# Schematic_v36.net
KiCad netlist of a schematic drawn in EAGLE
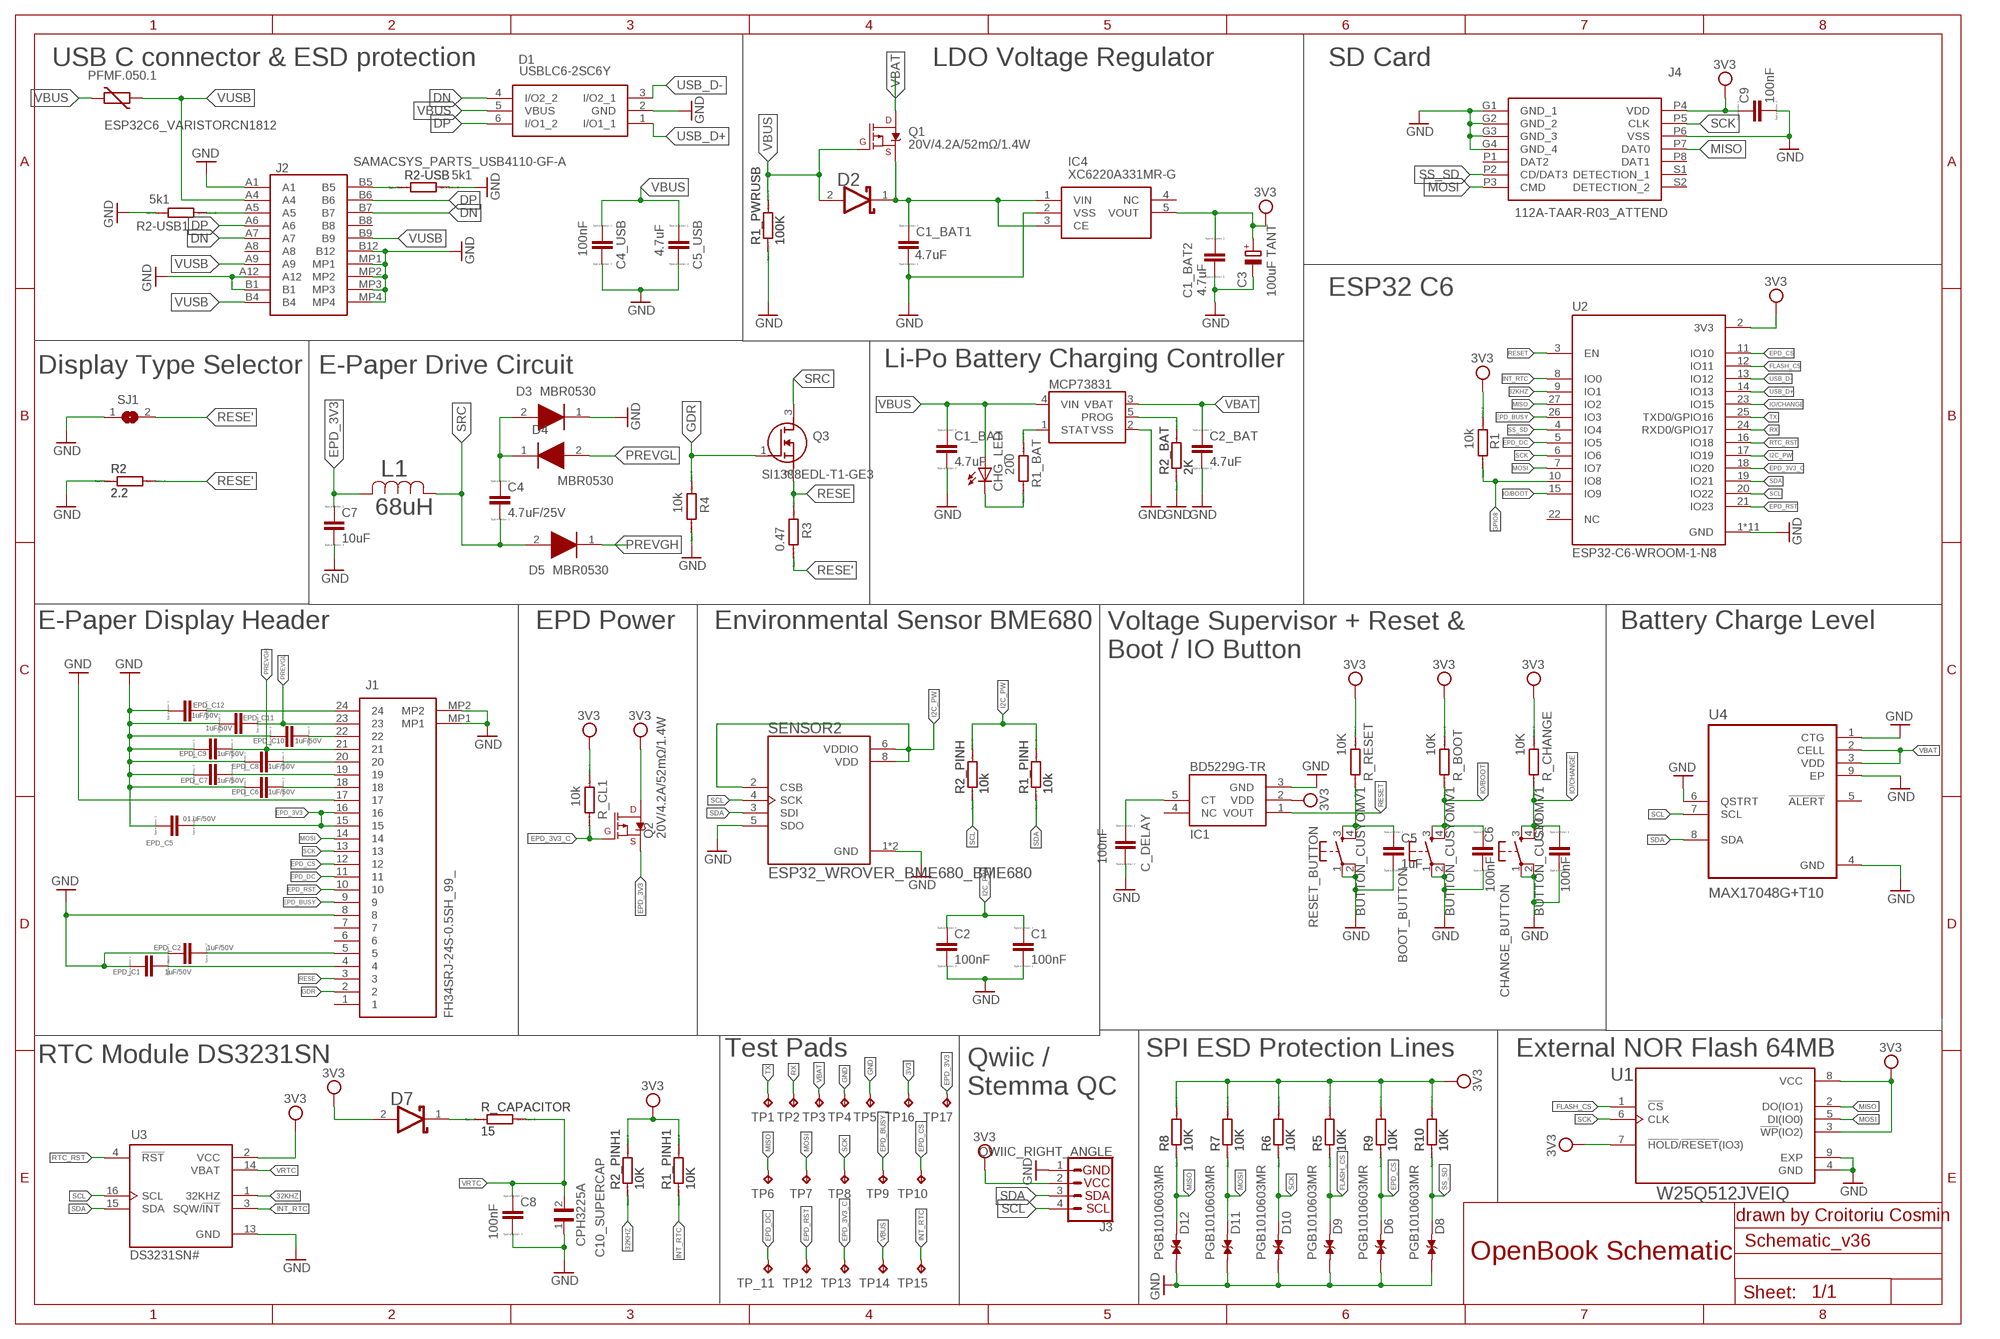
[diagram p0: schematic, sheet 1]

(export (version "E")
  (design (tool "Eeschema 10.0.6"))
  (components
    (comp (ref "BOOT_BUTTON")
      (value "BUTTON_CUSYOMV1")
      (footprint "eagle-import:MYBUTTON")
      (libsource (lib "eagle-import") (part "BUTTON_CUSYOMV1"))
    )
    (comp (ref "C1")
      (value "100nF")
      (footprint "eagle-import:EAGLE-LTSPICE_C0402")
      (libsource (lib "eagle-import") (part "EAGLE-LTSPICE_CC0402"))
    )
    (comp (ref "C1_BAT")
      (value "4.7uF")
      (footprint "eagle-import:EAGLE-LTSPICE_C0402")
      (libsource (lib "eagle-import") (part "EAGLE-LTSPICE_CC0402"))
    )
    (comp (ref "C1_BAT1")
      (value "4.7uF")
      (footprint "eagle-import:EAGLE-LTSPICE_C0402")
      (libsource (lib "eagle-import") (part "ESP32_WROVER_EAGLE-LTSPICE_CC0402"))
    )
    (comp (ref "C1_BAT2")
      (value "4.7uF")
      (footprint "eagle-import:EAGLE-LTSPICE_C0402")
      (libsource (lib "eagle-import") (part "ESP32_WROVER_EAGLE-LTSPICE_CC0402"))
    )
    (comp (ref "C2")
      (value "100nF")
      (footprint "eagle-import:EAGLE-LTSPICE_C0402")
      (libsource (lib "eagle-import") (part "EAGLE-LTSPICE_CC0402"))
    )
    (comp (ref "C2_BAT")
      (value "4.7uF")
      (footprint "eagle-import:EAGLE-LTSPICE_C0402")
      (libsource (lib "eagle-import") (part "EAGLE-LTSPICE_CC0402"))
    )
    (comp (ref "C3")
      (value "100uF TANT")
      (footprint "eagle-import:RCL_CT3528")
      (libsource (lib "eagle-import") (part "RCL_CPOL-EUCT3528"))
    )
    (comp (ref "C4")
      (value "4.7uF/25V")
      (footprint "eagle-import:EAGLE-LTSPICE_C0402")
      (libsource (lib "eagle-import") (part "EAGLE-LTSPICE_CC0402"))
    )
    (comp (ref "C4_USB")
      (value "100nF")
      (footprint "eagle-import:EAGLE-LTSPICE_C0402")
      (libsource (lib "eagle-import") (part "EAGLE-LTSPICE_CC0402"))
    )
    (comp (ref "C5")
      (value "1uF")
      (footprint "eagle-import:EAGLE-LTSPICE_C0402")
      (libsource (lib "eagle-import") (part "EAGLE-LTSPICE_CC0402"))
    )
    (comp (ref "C5_USB")
      (value "4.7uF")
      (footprint "eagle-import:EAGLE-LTSPICE_C0402")
      (libsource (lib "eagle-import") (part "EAGLE-LTSPICE_CC0402"))
    )
    (comp (ref "C6")
      (value "100nF")
      (footprint "eagle-import:EAGLE-LTSPICE_C0402")
      (libsource (lib "eagle-import") (part "EAGLE-LTSPICE_CC0402"))
    )
    (comp (ref "C7")
      (value "10uF")
      (footprint "eagle-import:EAGLE-LTSPICE_C0402")
      (libsource (lib "eagle-import") (part "EAGLE-LTSPICE_CC0402"))
    )
    (comp (ref "C8")
      (value "100nF")
      (footprint "eagle-import:EAGLE-LTSPICE_C0402")
      (libsource (lib "eagle-import") (part "EAGLE-LTSPICE_CC0402"))
    )
    (comp (ref "C9")
      (value "100nF")
      (footprint "eagle-import:EAGLE-LTSPICE_C0402")
      (libsource (lib "eagle-import") (part "EAGLE-LTSPICE_CC0402"))
    )
    (comp (ref "C10")
      (value "100nF")
      (footprint "eagle-import:EAGLE-LTSPICE_C0402")
      (libsource (lib "eagle-import") (part "EAGLE-LTSPICE_CC0402"))
    )
    (comp (ref "C10_SUPERCAP")
      (value "CPH3225A")
      (footprint "eagle-import:CAPCP3225X100N")
      (fields (field (name "MF") "Seiko Instruments"))
      (libsource (lib "eagle-import") (part "CPH3225A"))
    )
    (comp (ref "CHANGE_BUTTON")
      (value "BUTTON_CUSYOMV1")
      (footprint "eagle-import:MYBUTTON")
      (libsource (lib "eagle-import") (part "BUTTON_CUSYOMV1"))
    )
    (comp (ref "CHG_LED")
      (value "ADAFRUIT_LEDCHIP-LED0603")
      (footprint "eagle-import:ADAFRUIT_CHIP-LED0603")
      (libsource (lib "eagle-import") (part "ADAFRUIT_LEDCHIP-LED0603"))
    )
    (comp (ref "C_DELAY")
      (value "100nF")
      (footprint "eagle-import:EAGLE-LTSPICE_C0402")
      (libsource (lib "eagle-import") (part "EAGLE-LTSPICE_CC0402"))
    )
    (comp (ref "D1")
      (value "USBLC6-2SC6Y")
      (footprint "eagle-import:SOT95P280X145-6N")
      (fields (field (name "MF") "STMicroelectronics"))
      (libsource (lib "eagle-import") (part "USBLC6-2SC6Y"))
    )
    (comp (ref "D2")
      (value "ESP32_WROVER_AVX---SD0805S020S1R0_AVX_SD0805S020S1R0_0_0AVX_SD0805S020S1R0_0_0")
      (footprint "eagle-import:ESP32_WROVER_AVX---SD0805S020S1R0_AVX_SD0805S020S1R0_0")
      (fields
        (field (name "DIGIKEY_PART_NUMBER") "478-7800-1-ND")
        (field (name "MF") "AVX")
        (field (name "MOUSER_PART_NUMBER") "581-SD0805S020S1R0")
      )
      (libsource (lib "eagle-import") (part "ESP32_WROVER_AVX---SD0805S020S1R0_AVX_SD0805S020S1R0_0_0AVX_SD0805S020S1R0_0_0"))
    )
    (comp (ref "D3")
      (value "MBR0530")
      (footprint "eagle-import:SOD3716X135N")
      (fields (field (name "MF") "ON Semiconductor"))
      (libsource (lib "eagle-import") (part "MBR0530"))
    )
    (comp (ref "D4")
      (value "MBR0530")
      (footprint "eagle-import:SOD3716X135N")
      (fields (field (name "MF") "ON Semiconductor"))
      (libsource (lib "eagle-import") (part "MBR0530"))
    )
    (comp (ref "D5")
      (value "MBR0530")
      (footprint "eagle-import:SOD3716X135N")
      (fields (field (name "MF") "ON Semiconductor"))
      (libsource (lib "eagle-import") (part "MBR0530"))
    )
    (comp (ref "D6")
      (value "PGB1010603MR")
      (footprint "eagle-import:DIOC1608X36N")
      (fields (field (name "MF") "Littelfuse Inc."))
      (libsource (lib "eagle-import") (part "PGB1010603MR"))
    )
    (comp (ref "D7")
      (value "ESP32_WROVER_AVX---SD0805S020S1R0_AVX_SD0805S020S1R0_0_0AVX_SD0805S020S1R0_0_0")
      (footprint "eagle-import:ESP32_WROVER_AVX---SD0805S020S1R0_AVX_SD0805S020S1R0_0")
      (fields
        (field (name "DIGIKEY_PART_NUMBER") "478-7800-1-ND")
        (field (name "MF") "AVX")
        (field (name "MOUSER_PART_NUMBER") "581-SD0805S020S1R0")
      )
      (libsource (lib "eagle-import") (part "ESP32_WROVER_AVX---SD0805S020S1R0_AVX_SD0805S020S1R0_0_0AVX_SD0805S020S1R0_0_0"))
    )
    (comp (ref "D8")
      (value "PGB1010603MR")
      (footprint "eagle-import:DIOC1608X36N")
      (fields (field (name "MF") "Littelfuse Inc."))
      (libsource (lib "eagle-import") (part "PGB1010603MR"))
    )
    (comp (ref "D9")
      (value "PGB1010603MR")
      (footprint "eagle-import:DIOC1608X36N")
      (fields (field (name "MF") "Littelfuse Inc."))
      (libsource (lib "eagle-import") (part "PGB1010603MR"))
    )
    (comp (ref "D10")
      (value "PGB1010603MR")
      (footprint "eagle-import:DIOC1608X36N")
      (fields (field (name "MF") "Littelfuse Inc."))
      (libsource (lib "eagle-import") (part "PGB1010603MR"))
    )
    (comp (ref "D11")
      (value "PGB1010603MR")
      (footprint "eagle-import:DIOC1608X36N")
      (fields (field (name "MF") "Littelfuse Inc."))
      (libsource (lib "eagle-import") (part "PGB1010603MR"))
    )
    (comp (ref "D12")
      (value "PGB1010603MR")
      (footprint "eagle-import:DIOC1608X36N")
      (fields (field (name "MF") "Littelfuse Inc."))
      (libsource (lib "eagle-import") (part "PGB1010603MR"))
    )
    (comp (ref "EPD_C1")
      (value "1uF/50V")
      (footprint "eagle-import:EAGLE-LTSPICE_C0402")
      (libsource (lib "eagle-import") (part "EAGLE-LTSPICE_CC0402"))
    )
    (comp (ref "EPD_C2")
      (value "1uF/50V")
      (footprint "eagle-import:EAGLE-LTSPICE_C0402")
      (libsource (lib "eagle-import") (part "EAGLE-LTSPICE_CC0402"))
    )
    (comp (ref "EPD_C5")
      (value "01.uF/50V")
      (footprint "eagle-import:EAGLE-LTSPICE_C0402")
      (libsource (lib "eagle-import") (part "EAGLE-LTSPICE_CC0402"))
    )
    (comp (ref "EPD_C6")
      (value "1uF/50V")
      (footprint "eagle-import:EAGLE-LTSPICE_C0402")
      (libsource (lib "eagle-import") (part "EAGLE-LTSPICE_CC0402"))
    )
    (comp (ref "EPD_C7")
      (value "1uF/50V")
      (footprint "eagle-import:EAGLE-LTSPICE_C0402")
      (libsource (lib "eagle-import") (part "EAGLE-LTSPICE_CC0402"))
    )
    (comp (ref "EPD_C8")
      (value "1uF/50V")
      (footprint "eagle-import:EAGLE-LTSPICE_C0402")
      (libsource (lib "eagle-import") (part "EAGLE-LTSPICE_CC0402"))
    )
    (comp (ref "EPD_C9")
      (value "1uF/50V")
      (footprint "eagle-import:EAGLE-LTSPICE_C0402")
      (libsource (lib "eagle-import") (part "EAGLE-LTSPICE_CC0402"))
    )
    (comp (ref "EPD_C10")
      (value "1uF/50V")
      (footprint "eagle-import:EAGLE-LTSPICE_C0402")
      (libsource (lib "eagle-import") (part "EAGLE-LTSPICE_CC0402"))
    )
    (comp (ref "EPD_C11")
      (value "1uF/50V")
      (footprint "eagle-import:EAGLE-LTSPICE_C0402")
      (libsource (lib "eagle-import") (part "EAGLE-LTSPICE_CC0402"))
    )
    (comp (ref "EPD_C12")
      (value "1uF/50V")
      (footprint "eagle-import:EAGLE-LTSPICE_C0402")
      (libsource (lib "eagle-import") (part "EAGLE-LTSPICE_CC0402"))
    )
    (comp (ref "IC1")
      (value "BD5229G-TR")
      (footprint "eagle-import:SOT95P280X125-5N")
      (fields (field (name "MOUSER_PART_NUMBER") "755-BD5229G-TR"))
      (libsource (lib "eagle-import") (part "BD5229G-TR"))
    )
    (comp (ref "IC4")
      (value "XC6220A331MR-G")
      (footprint "eagle-import:SOT95P280X120-5N")
      (fields (field (name "MOUSER_PART_NUMBER") "865-XC6220A331MR-G"))
      (libsource (lib "eagle-import") (part "XC6220A331MR-G"))
    )
    (comp (ref "J1")
      (value "FH34SRJ-24S-0.5SH_99_")
      (footprint "eagle-import:FH34SRJ24S05SH99")
      (fields
        (field (name "MANUFACTURER_PART_NUMBER") "FH34SRJ-24S-0.5SH(99)")
        (field (name "MOUSER_PART_NUMBER") "798-FH34SRJ24S05SH99")
      )
      (libsource (lib "eagle-import") (part "FH34SRJ-24S-0.5SH_99_"))
    )
    (comp (ref "J2")
      (value "SAMACSYS_PARTS_USB4110-GF-A")
      (footprint "eagle-import:SAMACSYS_PARTS_USB4110GFA")
      (fields
        (field (name "MANUFACTURER_PART_NUMBER") "USB4110-GF-A")
        (field (name "MOUSER_PART_NUMBER") "640-USB4110-GF-A")
      )
      (libsource (lib "eagle-import") (part "SAMACSYS_PARTS_USB4110-GF-A"))
    )
    (comp (ref "J3")
      (value "QWIIC_RIGHT_ANGLE")
      (footprint "eagle-import:JST04_1MM_RA")
      (libsource (lib "eagle-import") (part "QWIIC_CONNECTORJS-1MM"))
    )
    (comp (ref "J4")
      (value "112A-TAAR-R03_ATTEND")
      (footprint "eagle-import:112ATAARR03ATTEND")
      (fields (field (name "MANUFACTURER_PART_NUMBER") "112A-TAAR-R03 ATTEND"))
      (libsource (lib "eagle-import") (part "112A-TAAR-R03_ATTEND"))
    )
    (comp (ref "L1")
      (value "68uH")
      (footprint "eagle-import:IND_4828-WE-TPC_WRE")
      (fields
        (field (name "MANUFACTURER_PART_NUMBER") "744043680")
        (field (name "COPYRIGHT") "Copyright (C) 2024 Ultra Librarian. All rights reserved.")
      )
      (libsource (lib "eagle-import") (part "744043680IND_4828-WE-TPC_WRE"))
    )
    (comp (ref "MCP73831")
      (value "ESP32_WROVER_SPARKFUN-IC-POWER_MCP73831")
      (footprint "eagle-import:ESP32_WROVER_SPARKFUN-IC-POWER_SOT23-5")
      (libsource (lib "eagle-import") (part "ESP32_WROVER_SPARKFUN-IC-POWER_MCP73831"))
    )
    (comp (ref "PFMF.050.1")
      (value "ESP32C6_VARISTORCN1812")
      (footprint "eagle-import:ESP32C6_VARISTOR_CT_CN1812")
      (libsource (lib "eagle-import") (part "ESP32C6_VARISTORCN1812"))
    )
    (comp (ref "Q1")
      (value "20V/4.2A/52mΩ/1.4W")
      (footprint "eagle-import:ESP32_WROVER_SPARKFUN-DISCRETESEMI_SOT23-3")
      (libsource (lib "eagle-import") (part "ESP32_WROVER_SPARKFUN-DISCRETESEMI_MOSFET_PCH-DMG2305UX-7"))
    )
    (comp (ref "Q2")
      (value "20V/4.2A/52mΩ/1.4W")
      (footprint "eagle-import:ESP32_WROVER_SPARKFUN-DISCRETESEMI_SOT23-3")
      (libsource (lib "eagle-import") (part "ESP32_WROVER_SPARKFUN-DISCRETESEMI_MOSFET_PCH-DMG2305UX-7"))
    )
    (comp (ref "Q3")
      (value "SI1308EDL-T1-GE3")
      (footprint "eagle-import:SOT65P210X110-3N")
      (fields (field (name "MF") "Vishay Siliconix"))
      (libsource (lib "eagle-import") (part "SI1308EDL-T1-GE3"))
    )
    (comp (ref "R1")
      (value "10k")
      (footprint "eagle-import:ESP32_WROVER_EAGLE-LTSPICE_R0402")
      (libsource (lib "eagle-import") (part "ESP32_WROVER_EAGLE-LTSPICE_RR0402"))
    )
    (comp (ref "R1_BAT")
      (value "200")
      (footprint "eagle-import:ESP32_WROVER_EAGLE-LTSPICE_R0402")
      (libsource (lib "eagle-import") (part "ESP32_WROVER_EAGLE-LTSPICE_RR0402"))
    )
    (comp (ref "R1_PINH")
      (value "10k")
      (footprint "eagle-import:ESP32_WROVER_EAGLE-LTSPICE_R0402")
      (libsource (lib "eagle-import") (part "ESP32_WROVER_EAGLE-LTSPICE_RR0402"))
    )
    (comp (ref "R1_PINH1")
      (value "10K")
      (footprint "eagle-import:ESP32_WROVER_EAGLE-LTSPICE_R0402")
      (libsource (lib "eagle-import") (part "ESP32_WROVER_EAGLE-LTSPICE_RR0402"))
    )
    (comp (ref "R1_PWRUSB")
      (value "100K")
      (footprint "eagle-import:ESP32_WROVER_EAGLE-LTSPICE_R0402")
      (libsource (lib "eagle-import") (part "ESP32_WROVER_EAGLE-LTSPICE_RR0402"))
    )
    (comp (ref "R2")
      (value "2.2")
      (footprint "eagle-import:ESP32_WROVER_EAGLE-LTSPICE_R0402")
      (libsource (lib "eagle-import") (part "ESP32_WROVER_EAGLE-LTSPICE_RR0402"))
    )
    (comp (ref "R2-USB")
      (value "5k1")
      (footprint "eagle-import:ESP32_WROVER_EAGLE-LTSPICE_R0402")
      (libsource (lib "eagle-import") (part "ESP32_WROVER_EAGLE-LTSPICE_RR0402"))
    )
    (comp (ref "R2-USB1")
      (value "5k1")
      (footprint "eagle-import:ESP32_WROVER_EAGLE-LTSPICE_R0402")
      (libsource (lib "eagle-import") (part "ESP32_WROVER_EAGLE-LTSPICE_RR0402"))
    )
    (comp (ref "R2_BAT")
      (value "2K")
      (footprint "eagle-import:ESP32_WROVER_EAGLE-LTSPICE_R0402")
      (libsource (lib "eagle-import") (part "ESP32_WROVER_EAGLE-LTSPICE_RR0402"))
    )
    (comp (ref "R2_PINH")
      (value "10k")
      (footprint "eagle-import:ESP32_WROVER_EAGLE-LTSPICE_R0402")
      (libsource (lib "eagle-import") (part "ESP32_WROVER_EAGLE-LTSPICE_RR0402"))
    )
    (comp (ref "R2_PINH1")
      (value "10K")
      (footprint "eagle-import:ESP32_WROVER_EAGLE-LTSPICE_R0402")
      (libsource (lib "eagle-import") (part "ESP32_WROVER_EAGLE-LTSPICE_RR0402"))
    )
    (comp (ref "R3")
      (value "0.47")
      (footprint "eagle-import:ESP32_WROVER_EAGLE-LTSPICE_R0402")
      (libsource (lib "eagle-import") (part "ESP32_WROVER_EAGLE-LTSPICE_RR0402"))
    )
    (comp (ref "R4")
      (value "10k")
      (footprint "eagle-import:ESP32_WROVER_EAGLE-LTSPICE_R0402")
      (libsource (lib "eagle-import") (part "ESP32_WROVER_EAGLE-LTSPICE_RR0402"))
    )
    (comp (ref "R5")
      (value "10K")
      (footprint "eagle-import:ESP32_WROVER_EAGLE-LTSPICE_R0402")
      (libsource (lib "eagle-import") (part "ESP32_WROVER_EAGLE-LTSPICE_RR0402"))
    )
    (comp (ref "R6")
      (value "10K")
      (footprint "eagle-import:ESP32_WROVER_EAGLE-LTSPICE_R0402")
      (libsource (lib "eagle-import") (part "ESP32_WROVER_EAGLE-LTSPICE_RR0402"))
    )
    (comp (ref "R7")
      (value "10K")
      (footprint "eagle-import:ESP32_WROVER_EAGLE-LTSPICE_R0402")
      (libsource (lib "eagle-import") (part "ESP32_WROVER_EAGLE-LTSPICE_RR0402"))
    )
    (comp (ref "R8")
      (value "10K")
      (footprint "eagle-import:ESP32_WROVER_EAGLE-LTSPICE_R0402")
      (libsource (lib "eagle-import") (part "ESP32_WROVER_EAGLE-LTSPICE_RR0402"))
    )
    (comp (ref "R9")
      (value "10K")
      (footprint "eagle-import:ESP32_WROVER_EAGLE-LTSPICE_R0402")
      (libsource (lib "eagle-import") (part "ESP32_WROVER_EAGLE-LTSPICE_RR0402"))
    )
    (comp (ref "R10")
      (value "10K")
      (footprint "eagle-import:ESP32_WROVER_EAGLE-LTSPICE_R0402")
      (libsource (lib "eagle-import") (part "ESP32_WROVER_EAGLE-LTSPICE_RR0402"))
    )
    (comp (ref "RESET_BUTTON")
      (value "BUTTON_CUSYOMV1")
      (footprint "eagle-import:MYBUTTON")
      (libsource (lib "eagle-import") (part "BUTTON_CUSYOMV1"))
    )
    (comp (ref "R_BOOT")
      (value "10K")
      (footprint "eagle-import:ESP32_WROVER_EAGLE-LTSPICE_R0402")
      (libsource (lib "eagle-import") (part "ESP32_WROVER_EAGLE-LTSPICE_RR0402"))
    )
    (comp (ref "R_CAPACITOR")
      (value "15")
      (footprint "eagle-import:ESP32_WROVER_EAGLE-LTSPICE_R0402")
      (libsource (lib "eagle-import") (part "ESP32_WROVER_EAGLE-LTSPICE_RR0402"))
    )
    (comp (ref "R_CHANGE")
      (value "10K")
      (footprint "eagle-import:ESP32_WROVER_EAGLE-LTSPICE_R0402")
      (libsource (lib "eagle-import") (part "ESP32_WROVER_EAGLE-LTSPICE_RR0402"))
    )
    (comp (ref "R_CL1")
      (value "10k")
      (footprint "eagle-import:ESP32_WROVER_EAGLE-LTSPICE_R0402")
      (libsource (lib "eagle-import") (part "ESP32_WROVER_EAGLE-LTSPICE_RR0402"))
    )
    (comp (ref "R_RESET")
      (value "10K")
      (footprint "eagle-import:ESP32_WROVER_EAGLE-LTSPICE_R0402")
      (libsource (lib "eagle-import") (part "ESP32_WROVER_EAGLE-LTSPICE_RR0402"))
    )
    (comp (ref "SENSOR2")
      (value "ESP32_WROVER_BME680_BME680")
      (footprint "eagle-import:ESP32_WROVER_BME680_PSON80P300X300X100-8N")
      (fields (field (name "MF") "Bosch Sensortec") (field (name "MP") "BME680"))
      (libsource (lib "eagle-import") (part "ESP32_WROVER_BME680_BME680"))
    )
    (comp (ref "SJ1") (value "SJ") (footprint "eagle-import:SJ") (libsource (lib "eagle-import") (part "SJ")))
    (comp (ref "TP1")
      (value "TPTP20R")
      (footprint "eagle-import:TP20R")
      (libsource (lib "eagle-import") (part "TPTP20R"))
    )
    (comp (ref "TP2")
      (value "TPTP20R")
      (footprint "eagle-import:TP20R")
      (libsource (lib "eagle-import") (part "TPTP20R"))
    )
    (comp (ref "TP3")
      (value "TPTP20R")
      (footprint "eagle-import:TP20R")
      (libsource (lib "eagle-import") (part "TPTP20R"))
    )
    (comp (ref "TP4")
      (value "TPTP20R")
      (footprint "eagle-import:TP20R")
      (libsource (lib "eagle-import") (part "TPTP20R"))
    )
    (comp (ref "TP5")
      (value "TPTP20R")
      (footprint "eagle-import:TP20R")
      (libsource (lib "eagle-import") (part "TPTP20R"))
    )
    (comp (ref "TP6")
      (value "TPTP20R")
      (footprint "eagle-import:TP20R")
      (libsource (lib "eagle-import") (part "TPTP20R"))
    )
    (comp (ref "TP7")
      (value "TPTP20R")
      (footprint "eagle-import:TP20R")
      (libsource (lib "eagle-import") (part "TPTP20R"))
    )
    (comp (ref "TP8")
      (value "TPTP20R")
      (footprint "eagle-import:TP20R")
      (libsource (lib "eagle-import") (part "TPTP20R"))
    )
    (comp (ref "TP9")
      (value "TPTP20R")
      (footprint "eagle-import:TP20R")
      (libsource (lib "eagle-import") (part "TPTP20R"))
    )
    (comp (ref "TP10")
      (value "TPTP20R")
      (footprint "eagle-import:TP20R")
      (libsource (lib "eagle-import") (part "TPTP20R"))
    )
    (comp (ref "TP12")
      (value "TPTP20R")
      (footprint "eagle-import:TP20R")
      (libsource (lib "eagle-import") (part "TPTP20R"))
    )
    (comp (ref "TP13")
      (value "TPTP20R")
      (footprint "eagle-import:TP20R")
      (libsource (lib "eagle-import") (part "TPTP20R"))
    )
    (comp (ref "TP14")
      (value "TPTP20R")
      (footprint "eagle-import:TP20R")
      (libsource (lib "eagle-import") (part "TPTP20R"))
    )
    (comp (ref "TP15")
      (value "TPTP20R")
      (footprint "eagle-import:TP20R")
      (libsource (lib "eagle-import") (part "TPTP20R"))
    )
    (comp (ref "TP16")
      (value "TPTP20R")
      (footprint "eagle-import:TP20R")
      (libsource (lib "eagle-import") (part "TPTP20R"))
    )
    (comp (ref "TP17")
      (value "TPTP20R")
      (footprint "eagle-import:TP20R")
      (libsource (lib "eagle-import") (part "TPTP20R"))
    )
    (comp (ref "TP_11")
      (value "TPTP20R")
      (footprint "eagle-import:TP20R")
      (libsource (lib "eagle-import") (part "TPTP20R"))
    )
    (comp (ref "U1")
      (value "W25Q512JVEIQ")
      (footprint "eagle-import:SON127P600X800X80-9N")
      (fields (field (name "MF") "Winbond Electronics"))
      (libsource (lib "eagle-import") (part "W25Q512JVEIQ"))
    )
    (comp (ref "U2")
      (value "ESP32-C6-WROOM-1-N8")
      (footprint "eagle-import:XCVR_ESP32-C6-WROOM-1-N8")
      (fields (field (name "MF") "Espressif Systems"))
      (libsource (lib "eagle-import") (part "ESP32-C6-WROOM-1-N8"))
    )
    (comp (ref "U3")
      (value "DS3231SN#")
      (footprint "eagle-import:SOIC127P1032X265-16N")
      (fields (field (name "MF") "Analog Devices"))
      (libsource (lib "eagle-import") (part "DS3231SN#"))
    )
    (comp (ref "U4")
      (value "MAX17048G+T10")
      (footprint "eagle-import:SON50P200X200X80-9N")
      (fields (field (name "MF") "Analog Devices"))
      (libsource (lib "eagle-import") (part "MAX17048G+T10"))
    )
  )
  (nets
    (net (code "1") (name "3V3") (class "Default")
      (node (ref "C1_BAT2") (pin "2") (pinfunction "2_2") (pintype "passive"))
      (node (ref "C3") (pin "+") (pinfunction "+_+") (pintype "passive"))
      (node (ref "C9") (pin "1") (pinfunction "1_1") (pintype "passive"))
      (node (ref "D7") (pin "2") (pinfunction "ANODE_2") (pintype "bidirectional"))
      (node (ref "IC1") (pin "2") (pinfunction "VDD_2") (pintype "bidirectional"))
      (node (ref "IC4") (pin "5") (pinfunction "VOUT_5") (pintype "bidirectional"))
      (node (ref "J3") (pin "2") (pinfunction "2_2") (pintype "power_in"))
      (node (ref "J4") (pin "P4") (pinfunction "VDD_P4") (pintype "bidirectional"))
      (node (ref "Q2") (pin "3") (pinfunction "D_3") (pintype "bidirectional"))
      (node (ref "R1") (pin "2") (pinfunction "2_2") (pintype "passive"))
      (node (ref "R10") (pin "2") (pinfunction "2_2") (pintype "passive"))
      (node (ref "R1_PINH1") (pin "2") (pinfunction "2_2") (pintype "passive"))
      (node (ref "R2_PINH1") (pin "2") (pinfunction "2_2") (pintype "passive"))
      (node (ref "R5") (pin "2") (pinfunction "2_2") (pintype "passive"))
      (node (ref "R6") (pin "2") (pinfunction "2_2") (pintype "passive"))
      (node (ref "R7") (pin "2") (pinfunction "2_2") (pintype "passive"))
      (node (ref "R8") (pin "2") (pinfunction "2_2") (pintype "passive"))
      (node (ref "R9") (pin "2") (pinfunction "2_2") (pintype "passive"))
      (node (ref "R_BOOT") (pin "2") (pinfunction "2_2") (pintype "passive"))
      (node (ref "R_CHANGE") (pin "2") (pinfunction "2_2") (pintype "passive"))
      (node (ref "R_CL1") (pin "2") (pinfunction "2_2") (pintype "passive"))
      (node (ref "R_RESET") (pin "2") (pinfunction "2_2") (pintype "passive"))
      (node (ref "TP16") (pin "TP") (pinfunction "TP_TP") (pintype "input"))
      (node (ref "U1") (pin "3") (pinfunction "~{WP}(IO2)_3") (pintype "bidirectional"))
      (node (ref "U1") (pin "7") (pinfunction "~{HOLD}/~{RESET}(IO3)_7") (pintype "bidirectional"))
      (node (ref "U1") (pin "8") (pinfunction "VCC_8") (pintype "power_in"))
      (node (ref "U2") (pin "2") (pinfunction "3V3_2") (pintype "power_in"))
      (node (ref "U3") (pin "2") (pinfunction "VCC_2") (pintype "power_in"))
    )
    (net (code "2") (name "32KHZ") (class "Default")
      (node (ref "R2_PINH1") (pin "1") (pinfunction "1_1") (pintype "passive"))
      (node (ref "U2") (pin "9") (pinfunction "IO1_9") (pintype "bidirectional"))
      (node (ref "U3") (pin "1") (pinfunction "32KHZ_1") (pintype "output"))
    )
    (net (code "3") (name "DN") (class "Default")
      (node (ref "D1") (pin "4") (pinfunction "I/O2_2_4") (pintype "bidirectional"))
      (node (ref "J2") (pin "A7") (pinfunction "A7_A7") (pintype "bidirectional"))
      (node (ref "J2") (pin "B7") (pinfunction "B7_B7") (pintype "bidirectional"))
    )
    (net (code "4") (name "DP") (class "Default")
      (node (ref "D1") (pin "6") (pinfunction "I/O1_2_6") (pintype "bidirectional"))
      (node (ref "J2") (pin "A6") (pinfunction "A6_A6") (pintype "bidirectional"))
      (node (ref "J2") (pin "B6") (pinfunction "B6_B6") (pintype "bidirectional"))
    )
    (net (code "5") (name "EPD_3V3") (class "Default")
      (node (ref "C7") (pin "1") (pinfunction "1_1") (pintype "passive"))
      (node (ref "EPD_C5") (pin "2") (pinfunction "2_2") (pintype "passive"))
      (node (ref "J1") (pin "15") (pinfunction "15_15") (pintype "bidirectional"))
      (node (ref "J1") (pin "16") (pinfunction "16_16") (pintype "bidirectional"))
      (node (ref "L1") (pin "2") (pinfunction "2_2") (pintype "passive"))
      (node (ref "Q2") (pin "2") (pinfunction "S_2") (pintype "bidirectional"))
      (node (ref "TP17") (pin "TP") (pinfunction "TP_TP") (pintype "input"))
    )
    (net (code "6") (name "EPD_3V3_C") (class "Default")
      (node (ref "Q2") (pin "1") (pinfunction "G_1") (pintype "bidirectional"))
      (node (ref "R_CL1") (pin "1") (pinfunction "1_1") (pintype "passive"))
      (node (ref "TP13") (pin "TP") (pinfunction "TP_TP") (pintype "input"))
      (node (ref "U2") (pin "18") (pinfunction "IO20_18") (pintype "bidirectional"))
    )
    (net (code "7") (name "EPD_BUSY") (class "Default")
      (node (ref "J1") (pin "9") (pinfunction "9_9") (pintype "bidirectional"))
      (node (ref "TP9") (pin "TP") (pinfunction "TP_TP") (pintype "input"))
      (node (ref "U2") (pin "26") (pinfunction "IO3_26") (pintype "bidirectional"))
    )
    (net (code "8") (name "EPD_CS") (class "Default")
      (node (ref "D6") (pin "2") (pinfunction "2_2") (pintype "passive"))
      (node (ref "J1") (pin "12") (pinfunction "12_12") (pintype "bidirectional"))
      (node (ref "R9") (pin "1") (pinfunction "1_1") (pintype "passive"))
      (node (ref "TP10") (pin "TP") (pinfunction "TP_TP") (pintype "input"))
      (node (ref "U2") (pin "11") (pinfunction "IO10_11") (pintype "bidirectional"))
    )
    (net (code "9") (name "EPD_DC") (class "Default")
      (node (ref "J1") (pin "11") (pinfunction "11_11") (pintype "bidirectional"))
      (node (ref "TP_11") (pin "TP") (pinfunction "TP_TP") (pintype "input"))
      (node (ref "U2") (pin "5") (pinfunction "IO5_5") (pintype "bidirectional"))
    )
    (net (code "10") (name "EPD_RST") (class "Default")
      (node (ref "J1") (pin "10") (pinfunction "10_10") (pintype "bidirectional"))
      (node (ref "TP12") (pin "TP") (pinfunction "TP_TP") (pintype "input"))
      (node (ref "U2") (pin "21") (pinfunction "IO23_21") (pintype "bidirectional"))
    )
    (net (code "11") (name "FLASH_CS") (class "Default")
      (node (ref "D9") (pin "2") (pinfunction "2_2") (pintype "passive"))
      (node (ref "R5") (pin "1") (pinfunction "1_1") (pintype "passive"))
      (node (ref "U1") (pin "1") (pinfunction "~{CS}_1") (pintype "input"))
      (node (ref "U2") (pin "12") (pinfunction "IO11_12") (pintype "bidirectional"))
    )
    (net (code "12") (name "GDR") (class "Default")
      (node (ref "J1") (pin "2") (pinfunction "2_2") (pintype "bidirectional"))
      (node (ref "Q3") (pin "1") (pinfunction "G_1") (pintype "bidirectional"))
      (node (ref "R4") (pin "2") (pinfunction "2_2") (pintype "passive"))
    )
    (net (code "13") (name "GND") (class "Default")
      (node (ref "BOOT_BUTTON") (pin "1") (pinfunction "1_1") (pintype "passive"))
      (node (ref "BOOT_BUTTON") (pin "2") (pinfunction "2_2") (pintype "passive"))
      (node (ref "C1") (pin "2") (pinfunction "2_2") (pintype "passive"))
      (node (ref "C10") (pin "2") (pinfunction "2_2") (pintype "passive"))
      (node (ref "C10_SUPERCAP") (pin "1") (pinfunction "1_1") (pintype "passive"))
      (node (ref "C1_BAT") (pin "2") (pinfunction "2_2") (pintype "passive"))
      (node (ref "C1_BAT1") (pin "1") (pinfunction "1_1") (pintype "passive"))
      (node (ref "C1_BAT2") (pin "1") (pinfunction "1_1") (pintype "passive"))
      (node (ref "C2") (pin "2") (pinfunction "2_2") (pintype "passive"))
      (node (ref "C2_BAT") (pin "2") (pinfunction "2_2") (pintype "passive"))
      (node (ref "C3") (pin "-") (pinfunction "-_-") (pintype "passive"))
      (node (ref "C4_USB") (pin "2") (pinfunction "2_2") (pintype "passive"))
      (node (ref "C5") (pin "2") (pinfunction "2_2") (pintype "passive"))
      (node (ref "C5_USB") (pin "2") (pinfunction "2_2") (pintype "passive"))
      (node (ref "C6") (pin "2") (pinfunction "2_2") (pintype "passive"))
      (node (ref "C7") (pin "2") (pinfunction "2_2") (pintype "passive"))
      (node (ref "C8") (pin "2") (pinfunction "2_2") (pintype "passive"))
      (node (ref "C9") (pin "2") (pinfunction "2_2") (pintype "passive"))
      (node (ref "CHANGE_BUTTON") (pin "1") (pinfunction "1_1") (pintype "passive"))
      (node (ref "CHANGE_BUTTON") (pin "2") (pinfunction "2_2") (pintype "passive"))
      (node (ref "C_DELAY") (pin "2") (pinfunction "2_2") (pintype "passive"))
      (node (ref "D1") (pin "2") (pinfunction "GND_2") (pintype "bidirectional"))
      (node (ref "D10") (pin "1") (pinfunction "1_1") (pintype "passive"))
      (node (ref "D11") (pin "1") (pinfunction "1_1") (pintype "passive"))
      (node (ref "D12") (pin "1") (pinfunction "1_1") (pintype "passive"))
      (node (ref "D3") (pin "1") (pinfunction "K_1") (pintype "bidirectional"))
      (node (ref "D6") (pin "1") (pinfunction "1_1") (pintype "passive"))
      (node (ref "D8") (pin "1") (pinfunction "1_1") (pintype "passive"))
      (node (ref "D9") (pin "1") (pinfunction "1_1") (pintype "passive"))
      (node (ref "EPD_C1") (pin "1") (pinfunction "1_1") (pintype "passive"))
      (node (ref "EPD_C10") (pin "1") (pinfunction "1_1") (pintype "passive"))
      (node (ref "EPD_C11") (pin "1") (pinfunction "1_1") (pintype "passive"))
      (node (ref "EPD_C12") (pin "1") (pinfunction "1_1") (pintype "passive"))
      (node (ref "EPD_C2") (pin "1") (pinfunction "1_1") (pintype "passive"))
      (node (ref "EPD_C5") (pin "1") (pinfunction "1_1") (pintype "passive"))
      (node (ref "EPD_C6") (pin "1") (pinfunction "1_1") (pintype "passive"))
      (node (ref "EPD_C7") (pin "1") (pinfunction "1_1") (pintype "passive"))
      (node (ref "EPD_C8") (pin "1") (pinfunction "1_1") (pintype "passive"))
      (node (ref "EPD_C9") (pin "1") (pinfunction "1_1") (pintype "passive"))
      (node (ref "IC1") (pin "3") (pinfunction "GND_3") (pintype "bidirectional"))
      (node (ref "IC4") (pin "2") (pinfunction "VSS_2") (pintype "bidirectional"))
      (node (ref "J1") (pin "17") (pinfunction "17_17") (pintype "bidirectional"))
      (node (ref "J1") (pin "8") (pinfunction "8_8") (pintype "bidirectional"))
      (node (ref "J1") (pin "MP1") (pinfunction "MP1_MP1") (pintype "bidirectional"))
      (node (ref "J1") (pin "MP2") (pinfunction "MP2_MP2") (pintype "bidirectional"))
      (node (ref "J2") (pin "A1") (pinfunction "A1_A1") (pintype "bidirectional"))
      (node (ref "J2") (pin "A12") (pinfunction "A12_A12") (pintype "bidirectional"))
      (node (ref "J2") (pin "B1") (pinfunction "B1_B1") (pintype "bidirectional"))
      (node (ref "J2") (pin "B12") (pinfunction "B12_B12") (pintype "bidirectional"))
      (node (ref "J2") (pin "MP1") (pinfunction "MP1_MP1") (pintype "bidirectional"))
      (node (ref "J2") (pin "MP2") (pinfunction "MP2_MP2") (pintype "bidirectional"))
      (node (ref "J2") (pin "MP3") (pinfunction "MP3_MP3") (pintype "bidirectional"))
      (node (ref "J2") (pin "MP4") (pinfunction "MP4_MP4") (pintype "bidirectional"))
      (node (ref "J3") (pin "1") (pinfunction "1_1") (pintype "power_in"))
      (node (ref "J4") (pin "G1") (pinfunction "GND_1_G1") (pintype "bidirectional"))
      (node (ref "J4") (pin "G2") (pinfunction "GND_2_G2") (pintype "bidirectional"))
      (node (ref "J4") (pin "G3") (pinfunction "GND_3_G3") (pintype "bidirectional"))
      (node (ref "J4") (pin "G4") (pinfunction "GND_4_G4") (pintype "bidirectional"))
      (node (ref "J4") (pin "P6") (pinfunction "VSS_P6") (pintype "bidirectional"))
      (node (ref "MCP73831") (pin "2") (pinfunction "VSS_2") (pintype "power_in"))
      (node (ref "R1_PWRUSB") (pin "1") (pinfunction "1_1") (pintype "passive"))
      (node (ref "R2") (pin "1") (pinfunction "1_1") (pintype "passive"))
      (node (ref "R2-USB") (pin "2") (pinfunction "2_2") (pintype "passive"))
      (node (ref "R2-USB1") (pin "1") (pinfunction "1_1") (pintype "passive"))
      (node (ref "R2_BAT") (pin "1") (pinfunction "1_1") (pintype "passive"))
      (node (ref "R4") (pin "1") (pinfunction "1_1") (pintype "passive"))
      (node (ref "RESET_BUTTON") (pin "1") (pinfunction "1_1") (pintype "passive"))
      (node (ref "RESET_BUTTON") (pin "2") (pinfunction "2_2") (pintype "passive"))
      (node (ref "SENSOR2") (pin "1") (pinfunction "GND_1") (pintype "power_in"))
      (node (ref "SENSOR2") (pin "5") (pinfunction "SDO_5") (pintype "bidirectional"))
      (node (ref "SENSOR2") (pin "7") (pinfunction "GND_7") (pintype "power_in"))
      (node (ref "SJ1") (pin "1") (pinfunction "1_1") (pintype "passive"))
      (node (ref "TP4") (pin "TP") (pinfunction "TP_TP") (pintype "input"))
      (node (ref "TP5") (pin "TP") (pinfunction "TP_TP") (pintype "input"))
      (node (ref "U1") (pin "4") (pinfunction "GND_4") (pintype "power_in"))
      (node (ref "U1") (pin "9") (pinfunction "EXP_9") (pintype "passive"))
      (node (ref "U2") (pin "1") (pinfunction "GND_1") (pintype "power_in"))
      (node (ref "U2") (pin "28") (pinfunction "GND_28") (pintype "power_in"))
      (node (ref "U2") (pin "29_1") (pinfunction "GND_29_1") (pintype "power_in"))
      (node (ref "U2") (pin "29_2") (pinfunction "GND_29_2") (pintype "power_in"))
      (node (ref "U2") (pin "29_3") (pinfunction "GND_29_3") (pintype "power_in"))
      (node (ref "U2") (pin "29_4") (pinfunction "GND_29_4") (pintype "power_in"))
      (node (ref "U2") (pin "29_5") (pinfunction "GND_29_5") (pintype "power_in"))
      (node (ref "U2") (pin "29_6") (pinfunction "GND_29_6") (pintype "power_in"))
      (node (ref "U2") (pin "29_7") (pinfunction "GND_29_7") (pintype "power_in"))
      (node (ref "U2") (pin "29_8") (pinfunction "GND_29_8") (pintype "power_in"))
      (node (ref "U2") (pin "29_9") (pinfunction "GND_29_9") (pintype "power_in"))
      (node (ref "U3") (pin "13") (pinfunction "GND_13") (pintype "power_in"))
      (node (ref "U4") (pin "1") (pinfunction "CTG_1") (pintype "power_in"))
      (node (ref "U4") (pin "4") (pinfunction "GND_4") (pintype "power_in"))
      (node (ref "U4") (pin "6") (pinfunction "QSTRT_6") (pintype "input"))
      (node (ref "U4") (pin "9") (pinfunction "EP_9") (pintype "power_in"))
    )
    (net (code "14") (name "GPIO8") (class "Default")
      (node (ref "R1") (pin "1") (pinfunction "1_1") (pintype "passive"))
      (node (ref "U2") (pin "10") (pinfunction "IO8_10") (pintype "bidirectional"))
    )
    (net (code "15") (name "I2C_PW") (class "Default")
      (node (ref "C1") (pin "1") (pinfunction "1_1") (pintype "passive"))
      (node (ref "C2") (pin "1") (pinfunction "1_1") (pintype "passive"))
      (node (ref "R1_PINH") (pin "2") (pinfunction "2_2") (pintype "passive"))
      (node (ref "R2_PINH") (pin "2") (pinfunction "2_2") (pintype "passive"))
      (node (ref "SENSOR2") (pin "2") (pinfunction "CSB_2") (pintype "input"))
      (node (ref "SENSOR2") (pin "6") (pinfunction "VDDIO_6") (pintype "power_in"))
      (node (ref "SENSOR2") (pin "8") (pinfunction "VDD_8") (pintype "power_in"))
      (node (ref "U2") (pin "17") (pinfunction "IO19_17") (pintype "bidirectional"))
    )
    (net (code "16") (name "INT_RTC") (class "Default")
      (node (ref "R1_PINH1") (pin "1") (pinfunction "1_1") (pintype "passive"))
      (node (ref "TP15") (pin "TP") (pinfunction "TP_TP") (pintype "input"))
      (node (ref "U2") (pin "8") (pinfunction "IO0_8") (pintype "bidirectional"))
      (node (ref "U3") (pin "3") (pinfunction "SQW/~{INT}_3") (pintype "output"))
    )
    (net (code "17") (name "IO{slash}BOOT") (class "Default")
      (node (ref "BOOT_BUTTON") (pin "3") (pinfunction "3_3") (pintype "passive"))
      (node (ref "BOOT_BUTTON") (pin "4") (pinfunction "4_4") (pintype "passive"))
      (node (ref "C6") (pin "1") (pinfunction "1_1") (pintype "passive"))
      (node (ref "R_BOOT") (pin "1") (pinfunction "1_1") (pintype "passive"))
      (node (ref "U2") (pin "15") (pinfunction "IO9_15") (pintype "bidirectional"))
    )
    (net (code "18") (name "IO{slash}CHANGE") (class "Default")
      (node (ref "C10") (pin "1") (pinfunction "1_1") (pintype "passive"))
      (node (ref "CHANGE_BUTTON") (pin "3") (pinfunction "3_3") (pintype "passive"))
      (node (ref "CHANGE_BUTTON") (pin "4") (pinfunction "4_4") (pintype "passive"))
      (node (ref "R_CHANGE") (pin "1") (pinfunction "1_1") (pintype "passive"))
      (node (ref "U2") (pin "23") (pinfunction "IO15_23") (pintype "bidirectional"))
    )
    (net (code "19") (name "MISO") (class "Default")
      (node (ref "D12") (pin "2") (pinfunction "2_2") (pintype "passive"))
      (node (ref "J4") (pin "P7") (pinfunction "DAT0_P7") (pintype "bidirectional"))
      (node (ref "R8") (pin "1") (pinfunction "1_1") (pintype "passive"))
      (node (ref "TP6") (pin "TP") (pinfunction "TP_TP") (pintype "input"))
      (node (ref "U1") (pin "2") (pinfunction "DO(IO1)_2") (pintype "bidirectional"))
      (node (ref "U2") (pin "27") (pinfunction "IO2_27") (pintype "bidirectional"))
    )
    (net (code "20") (name "MOSI") (class "Default")
      (node (ref "D11") (pin "2") (pinfunction "2_2") (pintype "passive"))
      (node (ref "J1") (pin "14") (pinfunction "14_14") (pintype "bidirectional"))
      (node (ref "J4") (pin "P3") (pinfunction "CMD_P3") (pintype "bidirectional"))
      (node (ref "R7") (pin "1") (pinfunction "1_1") (pintype "passive"))
      (node (ref "TP7") (pin "TP") (pinfunction "TP_TP") (pintype "input"))
      (node (ref "U1") (pin "5") (pinfunction "DI(IO0)_5") (pintype "bidirectional"))
      (node (ref "U2") (pin "7") (pinfunction "IO7_7") (pintype "bidirectional"))
    )
    (net (code "21") (name "Net-(C5-Pad1)") (class "Default")
      (node (ref "C5") (pin "1") (pinfunction "1_1") (pintype "passive"))
      (node (ref "RESET_BUTTON") (pin "3") (pinfunction "3_3") (pintype "passive"))
      (node (ref "RESET_BUTTON") (pin "4") (pinfunction "4_4") (pintype "passive"))
      (node (ref "R_RESET") (pin "1") (pinfunction "1_1") (pintype "passive"))
    )
    (net (code "22") (name "Net-(CHG_LED-PadC)") (class "Default")
      (node (ref "CHG_LED") (pin "C") (pinfunction "C_C") (pintype "passive"))
      (node (ref "R1_BAT") (pin "1") (pinfunction "1_1") (pintype "passive"))
    )
    (net (code "23") (name "Net-(D2-CATHODE)") (class "Default")
      (node (ref "C1_BAT1") (pin "2") (pinfunction "2_2") (pintype "passive"))
      (node (ref "D2") (pin "1") (pinfunction "CATHODE_1") (pintype "bidirectional"))
      (node (ref "IC4") (pin "1") (pinfunction "VIN_1") (pintype "bidirectional"))
      (node (ref "IC4") (pin "3") (pinfunction "CE_3") (pintype "bidirectional"))
      (node (ref "Q1") (pin "2") (pinfunction "S_2") (pintype "bidirectional"))
    )
    (net (code "24") (name "Net-(D3-A)") (class "Default")
      (node (ref "C4") (pin "1") (pinfunction "1_1") (pintype "passive"))
      (node (ref "D3") (pin "2") (pinfunction "A_2") (pintype "bidirectional"))
      (node (ref "D4") (pin "1") (pinfunction "K_1") (pintype "bidirectional"))
    )
    (net (code "25") (name "Net-(D7-CATHODE)") (class "Default")
      (node (ref "D7") (pin "1") (pinfunction "CATHODE_1") (pintype "bidirectional"))
      (node (ref "R_CAPACITOR") (pin "1") (pinfunction "1_1") (pintype "passive"))
    )
    (net (code "26") (name "Net-(EPD_C1-Pad2)") (class "Default")
      (node (ref "EPD_C1") (pin "2") (pinfunction "2_2") (pintype "passive"))
      (node (ref "J1") (pin "4") (pinfunction "4_4") (pintype "bidirectional"))
    )
    (net (code "27") (name "Net-(EPD_C2-Pad2)") (class "Default")
      (node (ref "EPD_C2") (pin "2") (pinfunction "2_2") (pintype "passive"))
      (node (ref "J1") (pin "5") (pinfunction "5_5") (pintype "bidirectional"))
    )
    (net (code "28") (name "Net-(EPD_C6-Pad2)") (class "Default")
      (node (ref "EPD_C6") (pin "2") (pinfunction "2_2") (pintype "passive"))
      (node (ref "J1") (pin "18") (pinfunction "18_18") (pintype "bidirectional"))
    )
    (net (code "29") (name "Net-(EPD_C7-Pad2)") (class "Default")
      (node (ref "EPD_C7") (pin "2") (pinfunction "2_2") (pintype "passive"))
      (node (ref "J1") (pin "19") (pinfunction "19_19") (pintype "bidirectional"))
    )
    (net (code "30") (name "Net-(EPD_C8-Pad2)") (class "Default")
      (node (ref "EPD_C8") (pin "2") (pinfunction "2_2") (pintype "passive"))
      (node (ref "J1") (pin "20") (pinfunction "20_20") (pintype "bidirectional"))
    )
    (net (code "31") (name "Net-(EPD_C10-Pad2)") (class "Default")
      (node (ref "EPD_C10") (pin "2") (pinfunction "2_2") (pintype "passive"))
      (node (ref "J1") (pin "22") (pinfunction "22_22") (pintype "bidirectional"))
    )
    (net (code "32") (name "Net-(EPD_C12-Pad2)") (class "Default")
      (node (ref "EPD_C12") (pin "2") (pinfunction "2_2") (pintype "passive"))
      (node (ref "J1") (pin "24") (pinfunction "24_24") (pintype "bidirectional"))
    )
    (net (code "33") (name "Net-(IC1-CT)") (class "Default")
      (node (ref "C_DELAY") (pin "1") (pinfunction "1_1") (pintype "passive"))
      (node (ref "IC1") (pin "5") (pinfunction "CT_5") (pintype "bidirectional"))
    )
    (net (code "34") (name "Net-(J2-PadA5)") (class "Default")
      (node (ref "J2") (pin "A5") (pinfunction "A5_A5") (pintype "bidirectional"))
      (node (ref "R2-USB1") (pin "2") (pinfunction "2_2") (pintype "passive"))
    )
    (net (code "35") (name "Net-(J2-PadB5)") (class "Default")
      (node (ref "J2") (pin "B5") (pinfunction "B5_B5") (pintype "bidirectional"))
      (node (ref "R2-USB") (pin "1") (pinfunction "1_1") (pintype "passive"))
    )
    (net (code "36") (name "Net-(MCP73831-PROG)") (class "Default")
      (node (ref "MCP73831") (pin "5") (pinfunction "PROG_5") (pintype "input"))
      (node (ref "R2_BAT") (pin "2") (pinfunction "2_2") (pintype "passive"))
    )
    (net (code "37") (name "Net-(MCP73831-STAT)") (class "Default")
      (node (ref "MCP73831") (pin "1") (pinfunction "STAT_1") (pintype "output"))
      (node (ref "R1_BAT") (pin "2") (pinfunction "2_2") (pintype "passive"))
    )
    (net (code "38") (name "PREVGH") (class "Default")
      (node (ref "D5") (pin "1") (pinfunction "K_1") (pintype "bidirectional"))
      (node (ref "EPD_C9") (pin "2") (pinfunction "2_2") (pintype "passive"))
      (node (ref "J1") (pin "21") (pinfunction "21_21") (pintype "bidirectional"))
    )
    (net (code "39") (name "PREVGL") (class "Default")
      (node (ref "D4") (pin "2") (pinfunction "A_2") (pintype "bidirectional"))
      (node (ref "EPD_C11") (pin "2") (pinfunction "2_2") (pintype "passive"))
      (node (ref "J1") (pin "23") (pinfunction "23_23") (pintype "bidirectional"))
    )
    (net (code "40") (name "RESE") (class "Default")
      (node (ref "J1") (pin "3") (pinfunction "3_3") (pintype "bidirectional"))
      (node (ref "Q3") (pin "2") (pinfunction "S_2") (pintype "bidirectional"))
      (node (ref "R3") (pin "2") (pinfunction "2_2") (pintype "passive"))
    )
    (net (code "41") (name "RESE'") (class "Default")
      (node (ref "R2") (pin "2") (pinfunction "2_2") (pintype "passive"))
      (node (ref "R3") (pin "1") (pinfunction "1_1") (pintype "passive"))
      (node (ref "SJ1") (pin "2") (pinfunction "2_2") (pintype "passive"))
    )
    (net (code "42") (name "RESET") (class "Default")
      (node (ref "IC1") (pin "1") (pinfunction "VOUT_1") (pintype "bidirectional"))
      (node (ref "U2") (pin "3") (pinfunction "EN_3") (pintype "input"))
    )
    (net (code "43") (name "RTC_RST") (class "Default")
      (node (ref "U2") (pin "16") (pinfunction "IO18_16") (pintype "bidirectional"))
      (node (ref "U3") (pin "4") (pinfunction "~{RST}_4") (pintype "input"))
    )
    (net (code "44") (name "RX") (class "Default")
      (node (ref "TP2") (pin "TP") (pinfunction "TP_TP") (pintype "input"))
      (node (ref "U2") (pin "24") (pinfunction "RXD0/GPIO17_24") (pintype "bidirectional"))
    )
    (net (code "45") (name "SCK") (class "Default")
      (node (ref "D10") (pin "2") (pinfunction "2_2") (pintype "passive"))
      (node (ref "J1") (pin "13") (pinfunction "13_13") (pintype "bidirectional"))
      (node (ref "J4") (pin "P5") (pinfunction "CLK_P5") (pintype "bidirectional"))
      (node (ref "R6") (pin "1") (pinfunction "1_1") (pintype "passive"))
      (node (ref "TP8") (pin "TP") (pinfunction "TP_TP") (pintype "input"))
      (node (ref "U1") (pin "6") (pinfunction "CLK_6") (pintype "input"))
      (node (ref "U2") (pin "6") (pinfunction "IO6_6") (pintype "bidirectional"))
    )
    (net (code "46") (name "SCL") (class "Default")
      (node (ref "J3") (pin "4") (pinfunction "4_4") (pintype "passive"))
      (node (ref "R2_PINH") (pin "1") (pinfunction "1_1") (pintype "passive"))
      (node (ref "SENSOR2") (pin "4") (pinfunction "SCK_4") (pintype "input"))
      (node (ref "U2") (pin "20") (pinfunction "IO22_20") (pintype "bidirectional"))
      (node (ref "U3") (pin "16") (pinfunction "SCL_16") (pintype "input"))
      (node (ref "U4") (pin "7") (pinfunction "SCL_7") (pintype "input"))
    )
    (net (code "47") (name "SDA") (class "Default")
      (node (ref "J3") (pin "3") (pinfunction "3_3") (pintype "passive"))
      (node (ref "R1_PINH") (pin "1") (pinfunction "1_1") (pintype "passive"))
      (node (ref "SENSOR2") (pin "3") (pinfunction "SDI_3") (pintype "bidirectional"))
      (node (ref "U2") (pin "19") (pinfunction "IO21_19") (pintype "bidirectional"))
      (node (ref "U3") (pin "15") (pinfunction "SDA_15") (pintype "bidirectional"))
      (node (ref "U4") (pin "8") (pinfunction "SDA_8") (pintype "bidirectional"))
    )
    (net (code "48") (name "SRC") (class "Default")
      (node (ref "C4") (pin "2") (pinfunction "2_2") (pintype "passive"))
      (node (ref "D5") (pin "2") (pinfunction "A_2") (pintype "bidirectional"))
      (node (ref "L1") (pin "1") (pinfunction "1_1") (pintype "passive"))
      (node (ref "Q3") (pin "3") (pinfunction "D_3") (pintype "bidirectional"))
    )
    (net (code "49") (name "SS_SD") (class "Default")
      (node (ref "D8") (pin "2") (pinfunction "2_2") (pintype "passive"))
      (node (ref "J4") (pin "P2") (pinfunction "CD/DAT3_P2") (pintype "bidirectional"))
      (node (ref "R10") (pin "1") (pinfunction "1_1") (pintype "passive"))
      (node (ref "U2") (pin "4") (pinfunction "IO4_4") (pintype "bidirectional"))
    )
    (net (code "50") (name "TX") (class "Default")
      (node (ref "TP1") (pin "TP") (pinfunction "TP_TP") (pintype "input"))
      (node (ref "U2") (pin "25") (pinfunction "TXD0/GPIO16_25") (pintype "bidirectional"))
    )
    (net (code "51") (name "USB_D+") (class "Default")
      (node (ref "D1") (pin "1") (pinfunction "I/O1_1_1") (pintype "bidirectional"))
      (node (ref "U2") (pin "14") (pinfunction "IO13_14") (pintype "bidirectional"))
    )
    (net (code "52") (name "USB_D-") (class "Default")
      (node (ref "D1") (pin "3") (pinfunction "I/O2_1_3") (pintype "bidirectional"))
      (node (ref "U2") (pin "13") (pinfunction "IO12_13") (pintype "bidirectional"))
    )
    (net (code "53") (name "VBAT") (class "Default")
      (node (ref "C2_BAT") (pin "1") (pinfunction "1_1") (pintype "passive"))
      (node (ref "MCP73831") (pin "3") (pinfunction "VBAT_3") (pintype "power_in"))
      (node (ref "Q1") (pin "3") (pinfunction "D_3") (pintype "bidirectional"))
      (node (ref "TP3") (pin "TP") (pinfunction "TP_TP") (pintype "input"))
      (node (ref "U4") (pin "2") (pinfunction "CELL_2") (pintype "power_in"))
      (node (ref "U4") (pin "3") (pinfunction "VDD_3") (pintype "power_in"))
    )
    (net (code "54") (name "VBUS") (class "Default")
      (node (ref "C1_BAT") (pin "1") (pinfunction "1_1") (pintype "passive"))
      (node (ref "C4_USB") (pin "1") (pinfunction "1_1") (pintype "passive"))
      (node (ref "C5_USB") (pin "1") (pinfunction "1_1") (pintype "passive"))
      (node (ref "CHG_LED") (pin "A") (pinfunction "A_A") (pintype "passive"))
      (node (ref "D1") (pin "5") (pinfunction "VBUS_5") (pintype "bidirectional"))
      (node (ref "D2") (pin "2") (pinfunction "ANODE_2") (pintype "bidirectional"))
      (node (ref "MCP73831") (pin "4") (pinfunction "VIN_4") (pintype "power_in"))
      (node (ref "PFMF.050.1") (pin "2") (pinfunction "2_2") (pintype "passive"))
      (node (ref "Q1") (pin "1") (pinfunction "G_1") (pintype "bidirectional"))
      (node (ref "R1_PWRUSB") (pin "2") (pinfunction "2_2") (pintype "passive"))
      (node (ref "TP14") (pin "TP") (pinfunction "TP_TP") (pintype "input"))
    )
    (net (code "55") (name "VRTC") (class "Default")
      (node (ref "C10_SUPERCAP") (pin "2") (pinfunction "2_2") (pintype "passive"))
      (node (ref "C8") (pin "1") (pinfunction "1_1") (pintype "passive"))
      (node (ref "R_CAPACITOR") (pin "2") (pinfunction "2_2") (pintype "passive"))
      (node (ref "U3") (pin "14") (pinfunction "VBAT_14") (pintype "power_in"))
    )
    (net (code "56") (name "VUSB") (class "Default")
      (node (ref "J2") (pin "A4") (pinfunction "A4_A4") (pintype "bidirectional"))
      (node (ref "J2") (pin "A9") (pinfunction "A9_A9") (pintype "bidirectional"))
      (node (ref "J2") (pin "B4") (pinfunction "B4_B4") (pintype "bidirectional"))
      (node (ref "J2") (pin "B9") (pinfunction "B9_B9") (pintype "bidirectional"))
      (node (ref "PFMF.050.1") (pin "1") (pinfunction "1_1") (pintype "passive"))
    )
    (net (code "57") (name "unconnected-(IC1-NC-Pad4)") (class "Default")
      (node (ref "IC1") (pin "4") (pinfunction "NC_4") (pintype "no_connect"))
    )
    (net (code "58") (name "unconnected-(IC4-NC-Pad4)") (class "Default")
      (node (ref "IC4") (pin "4") (pinfunction "NC_4") (pintype "no_connect"))
    )
    (net (code "59") (name "unconnected-(J1-Pad1)") (class "Default")
      (node (ref "J1") (pin "1") (pinfunction "1_1") (pintype "bidirectional"))
    )
    (net (code "60") (name "unconnected-(J1-Pad6)") (class "Default")
      (node (ref "J1") (pin "6") (pinfunction "6_6") (pintype "bidirectional"))
    )
    (net (code "61") (name "unconnected-(J1-Pad7)") (class "Default")
      (node (ref "J1") (pin "7") (pinfunction "7_7") (pintype "bidirectional"))
    )
    (net (code "62") (name "unconnected-(J2-PadA8)") (class "Default")
      (node (ref "J2") (pin "A8") (pinfunction "A8_A8") (pintype "bidirectional"))
    )
    (net (code "63") (name "unconnected-(J2-PadB8)") (class "Default")
      (node (ref "J2") (pin "B8") (pinfunction "B8_B8") (pintype "bidirectional"))
    )
    (net (code "64") (name "unconnected-(J4-DAT1-PadP8)") (class "Default")
      (node (ref "J4") (pin "P8") (pinfunction "DAT1_P8") (pintype "bidirectional"))
    )
    (net (code "65") (name "unconnected-(J4-DAT2-PadP1)") (class "Default")
      (node (ref "J4") (pin "P1") (pinfunction "DAT2_P1") (pintype "bidirectional"))
    )
    (net (code "66") (name "unconnected-(J4-DETECTION_1-PadS1)") (class "Default")
      (node (ref "J4") (pin "S1") (pinfunction "DETECTION_1_S1") (pintype "bidirectional"))
    )
    (net (code "67") (name "unconnected-(J4-DETECTION_2-PadS2)") (class "Default")
      (node (ref "J4") (pin "S2") (pinfunction "DETECTION_2_S2") (pintype "bidirectional"))
    )
    (net (code "68") (name "unconnected-(U2-NC-Pad22)") (class "Default")
      (node (ref "U2") (pin "22") (pinfunction "NC_22") (pintype "no_connect"))
    )
    (net (code "69") (name "unconnected-(U4-~{ALERT}-Pad5)") (class "Default")
      (node (ref "U4") (pin "5") (pinfunction "~{ALERT}_5") (pintype "output"))
    )
  )
)
